# 7segment.net
KiCad netlist of a schematic drawn in EAGLE
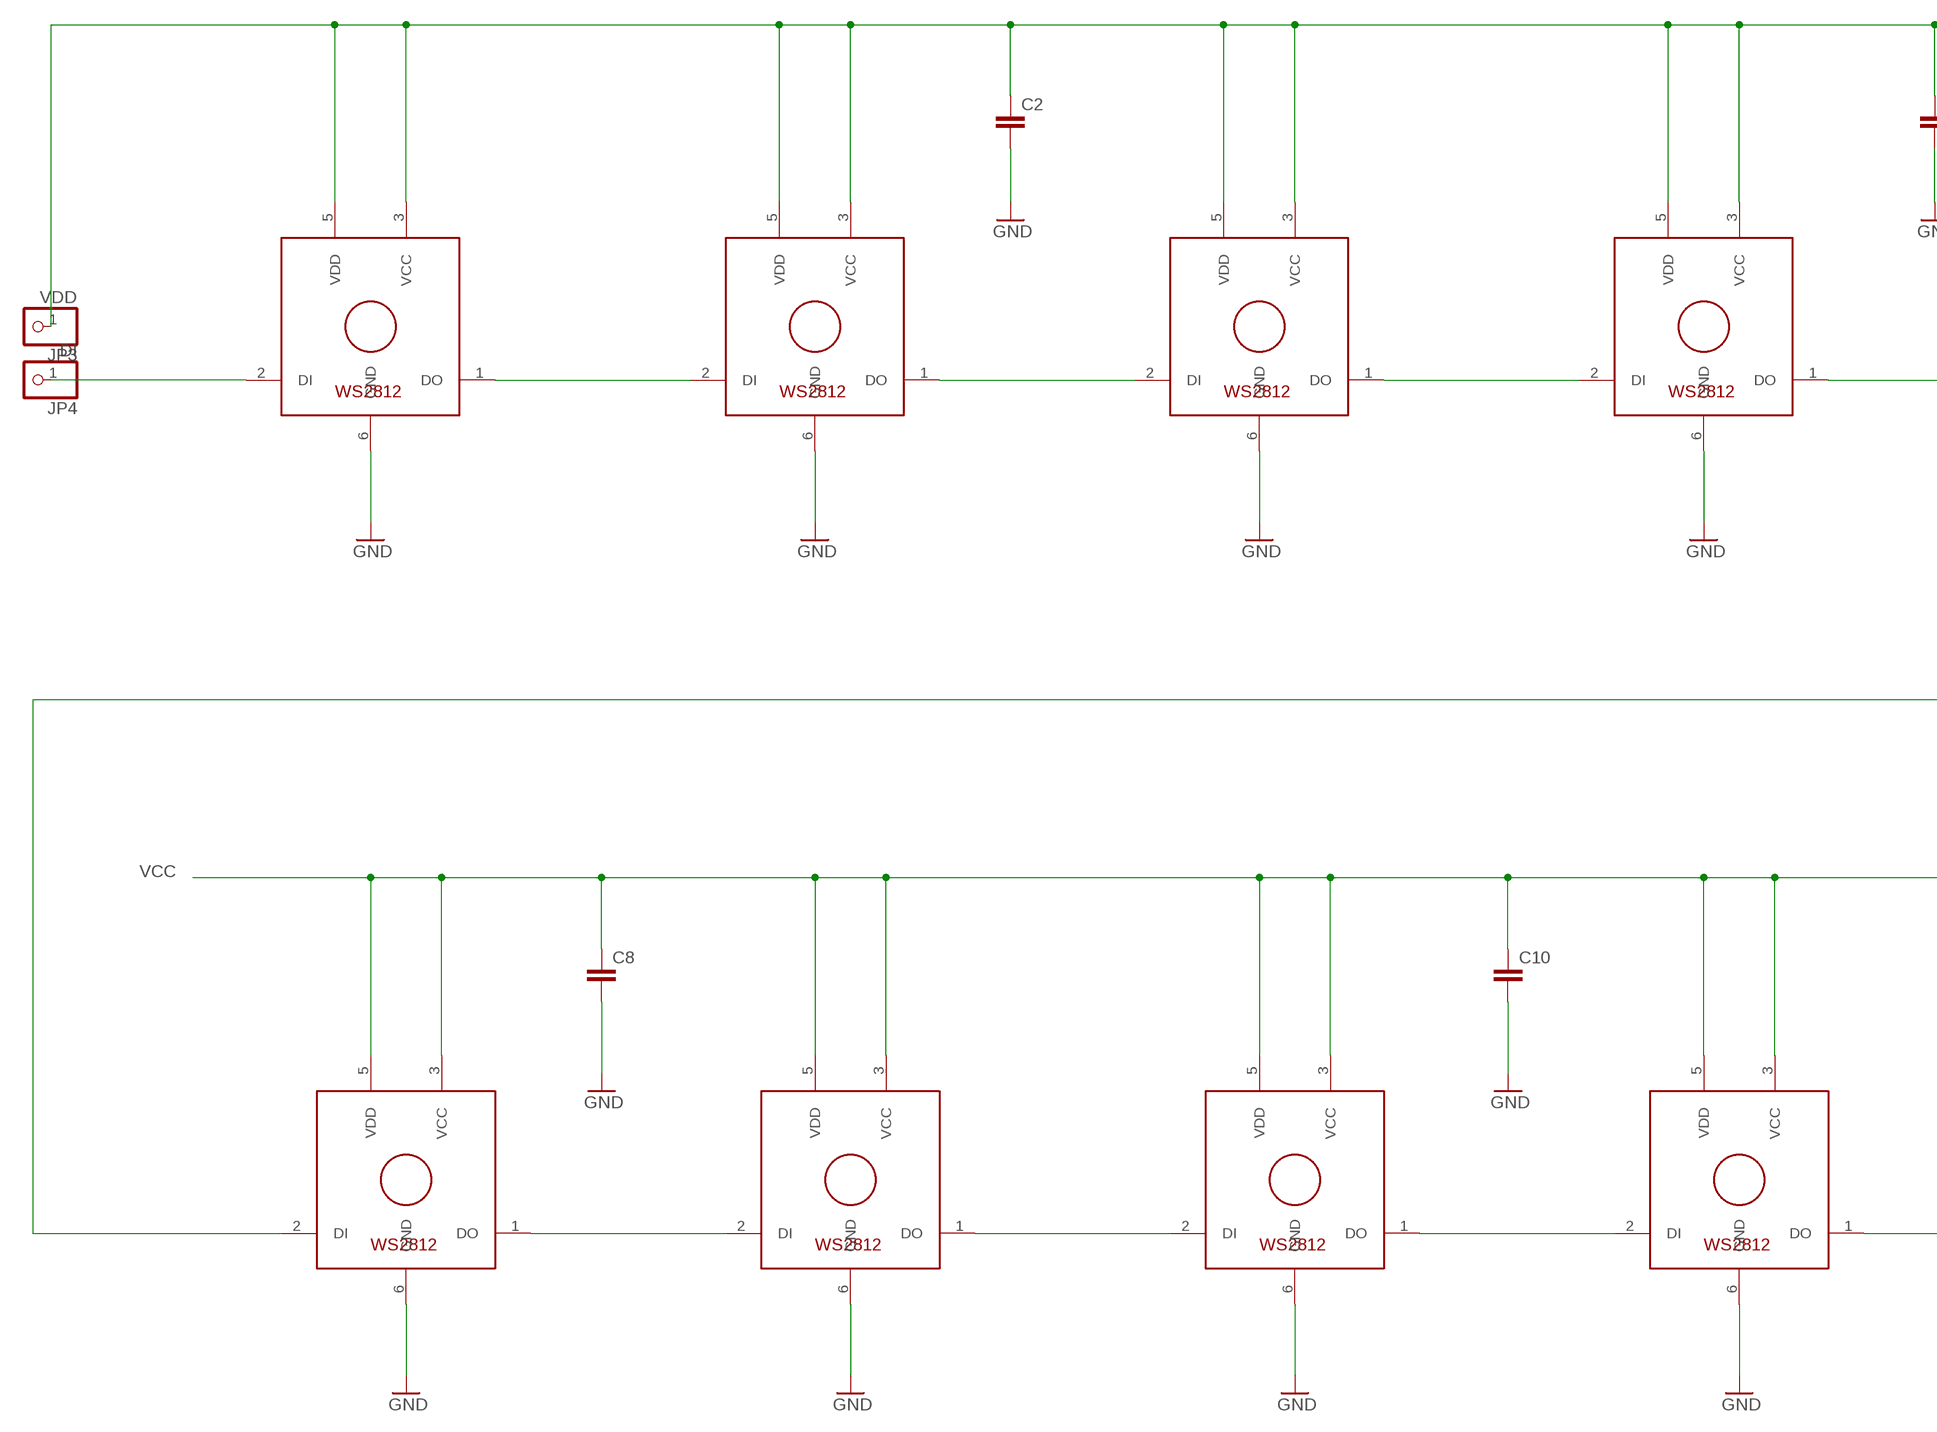
[diagram p0: schematic, sheet 1, part 1 of 2]
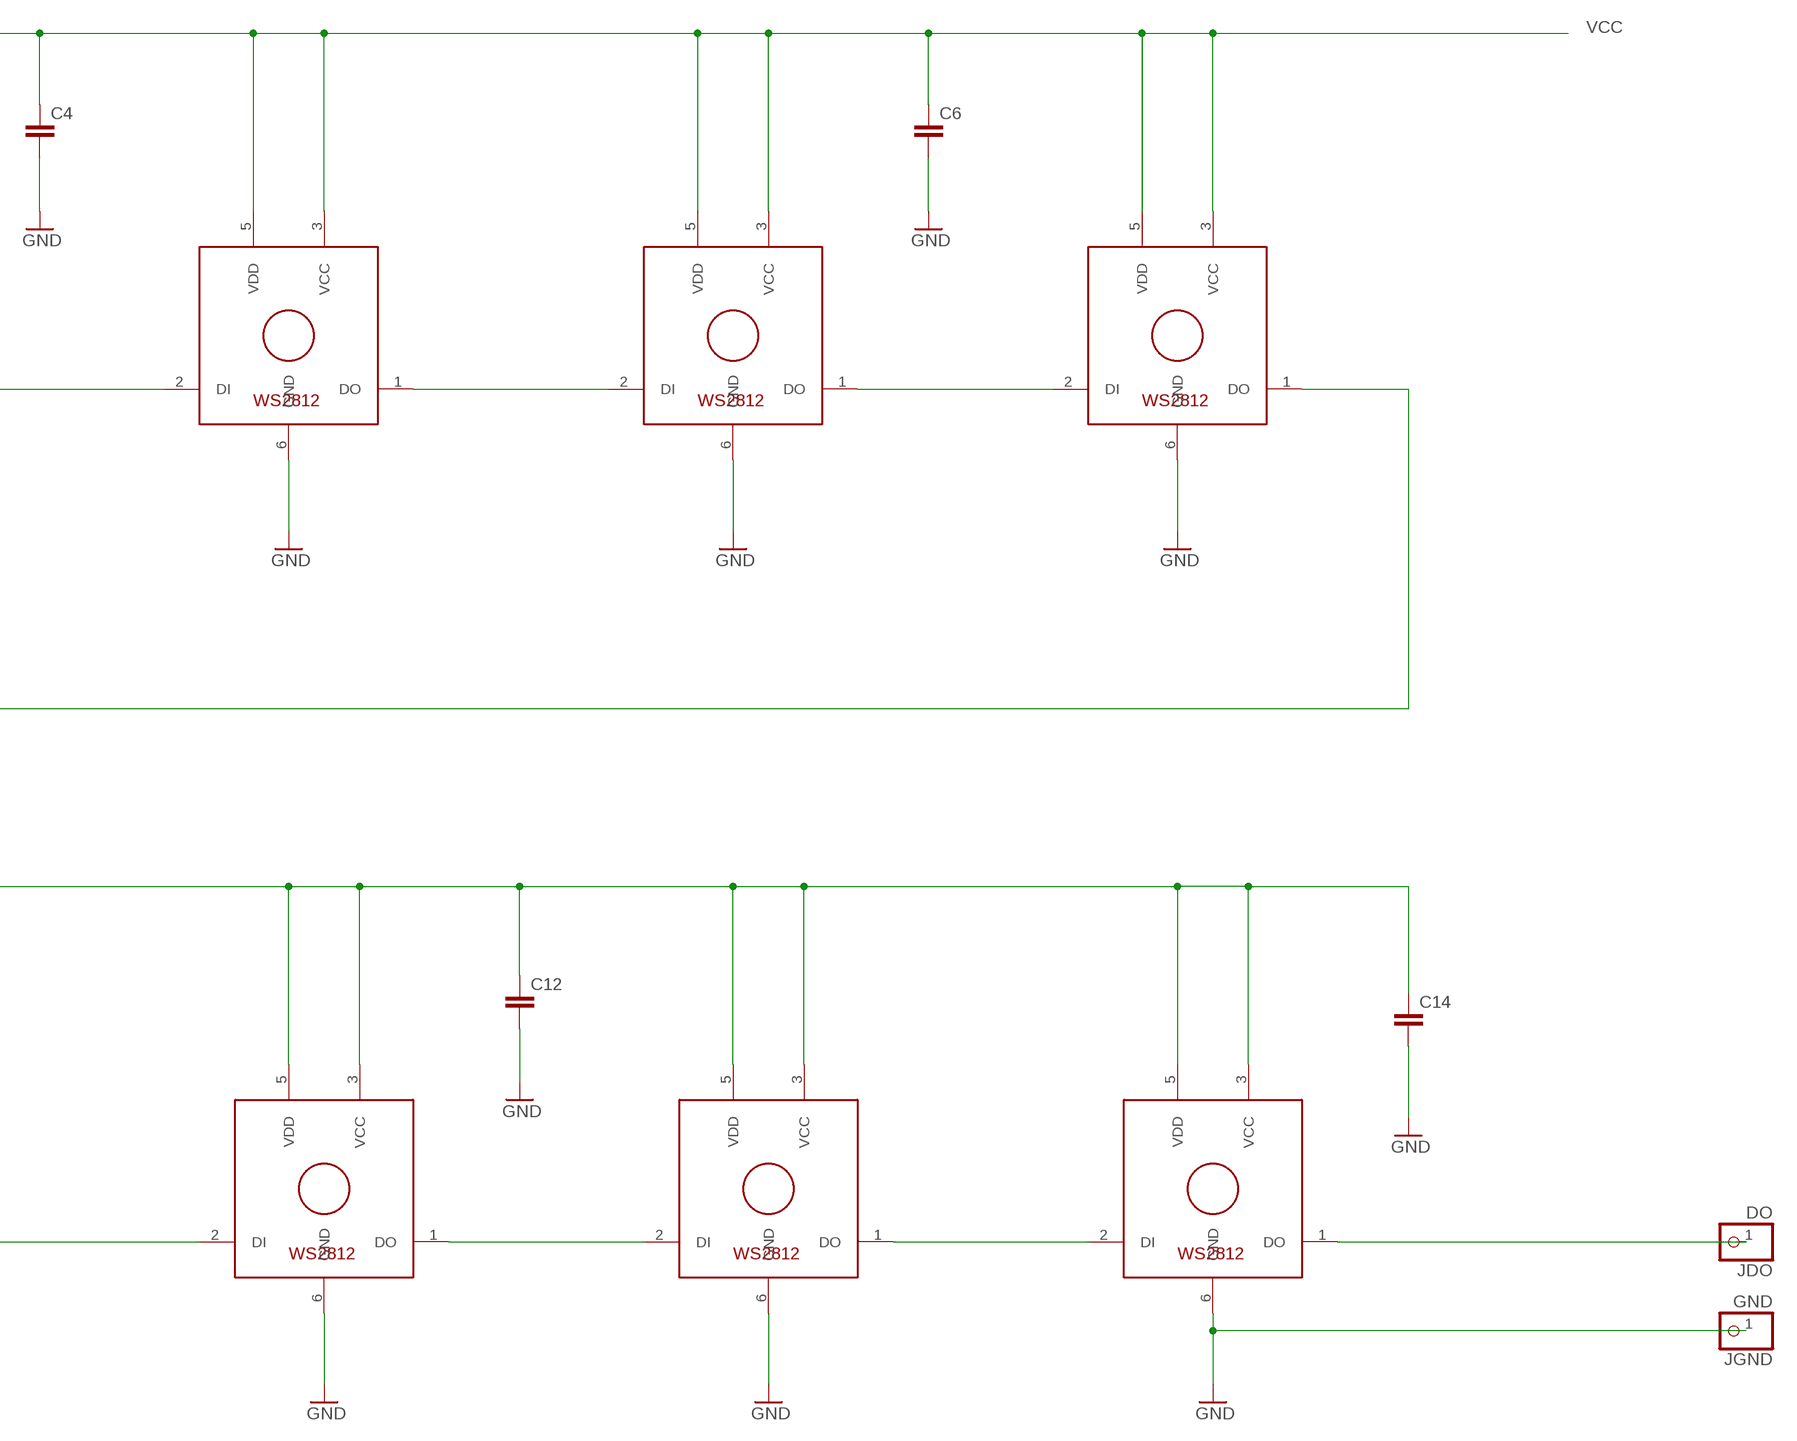
[diagram p1: schematic, sheet 1, part 2 of 2]

(export (version "E")
  (design (tool "Eeschema 10.0.6"))
  (components
    (comp (ref "C2")
      (value "C-EUC1206")
      (footprint "eagle-import:C1206")
      (libsource (lib "eagle-import") (part "C-EUC1206"))
    )
    (comp (ref "C4")
      (value "C-EUC1206")
      (footprint "eagle-import:C1206")
      (libsource (lib "eagle-import") (part "C-EUC1206"))
    )
    (comp (ref "C6")
      (value "C-EUC1206")
      (footprint "eagle-import:C1206")
      (libsource (lib "eagle-import") (part "C-EUC1206"))
    )
    (comp (ref "C8")
      (value "C-EUC1206")
      (footprint "eagle-import:C1206")
      (libsource (lib "eagle-import") (part "C-EUC1206"))
    )
    (comp (ref "C10")
      (value "C-EUC1206")
      (footprint "eagle-import:C1206")
      (libsource (lib "eagle-import") (part "C-EUC1206"))
    )
    (comp (ref "C12")
      (value "C-EUC1206")
      (footprint "eagle-import:C1206")
      (libsource (lib "eagle-import") (part "C-EUC1206"))
    )
    (comp (ref "C14")
      (value "C-EUC1206")
      (footprint "eagle-import:C1206")
      (libsource (lib "eagle-import") (part "C-EUC1206"))
    )
    (comp (ref "JDO")
      (value "DO")
      (footprint "eagle-import:1X01")
      (libsource (lib "eagle-import") (part "PINHD-1X1"))
    )
    (comp (ref "JGND")
      (value "GND")
      (footprint "eagle-import:1X01")
      (libsource (lib "eagle-import") (part "PINHD-1X1"))
    )
    (comp (ref "JP3")
      (value "VDD")
      (footprint "eagle-import:1X01")
      (libsource (lib "eagle-import") (part "PINHD-1X1"))
    )
    (comp (ref "JP4")
      (value "DI")
      (footprint "eagle-import:1X01")
      (libsource (lib "eagle-import") (part "PINHD-1X1"))
    )
    (comp (ref "U1")
      (value "WS2812")
      (footprint "eagle-import:WS2812")
      (libsource (lib "eagle-import") (part "WS2812"))
    )
    (comp (ref "U2")
      (value "WS2812")
      (footprint "eagle-import:WS2812")
      (libsource (lib "eagle-import") (part "WS2812"))
    )
    (comp (ref "U3")
      (value "WS2812")
      (footprint "eagle-import:WS2812")
      (libsource (lib "eagle-import") (part "WS2812"))
    )
    (comp (ref "U4")
      (value "WS2812")
      (footprint "eagle-import:WS2812")
      (libsource (lib "eagle-import") (part "WS2812"))
    )
    (comp (ref "U5")
      (value "WS2812")
      (footprint "eagle-import:WS2812")
      (libsource (lib "eagle-import") (part "WS2812"))
    )
    (comp (ref "U6")
      (value "WS2812")
      (footprint "eagle-import:WS2812")
      (libsource (lib "eagle-import") (part "WS2812"))
    )
    (comp (ref "U7")
      (value "WS2812")
      (footprint "eagle-import:WS2812")
      (libsource (lib "eagle-import") (part "WS2812"))
    )
    (comp (ref "U8")
      (value "WS2812")
      (footprint "eagle-import:WS2812")
      (libsource (lib "eagle-import") (part "WS2812"))
    )
    (comp (ref "U9")
      (value "WS2812")
      (footprint "eagle-import:WS2812")
      (libsource (lib "eagle-import") (part "WS2812"))
    )
    (comp (ref "U10")
      (value "WS2812")
      (footprint "eagle-import:WS2812")
      (libsource (lib "eagle-import") (part "WS2812"))
    )
    (comp (ref "U11")
      (value "WS2812")
      (footprint "eagle-import:WS2812")
      (libsource (lib "eagle-import") (part "WS2812"))
    )
    (comp (ref "U12")
      (value "WS2812")
      (footprint "eagle-import:WS2812")
      (libsource (lib "eagle-import") (part "WS2812"))
    )
    (comp (ref "U13")
      (value "WS2812")
      (footprint "eagle-import:WS2812")
      (libsource (lib "eagle-import") (part "WS2812"))
    )
    (comp (ref "U14")
      (value "WS2812")
      (footprint "eagle-import:WS2812")
      (libsource (lib "eagle-import") (part "WS2812"))
    )
  )
  (nets
    (net (code "1") (name "/VCC") (class "Default")
      (node (ref "C10") (pin "1") (pinfunction "1_1") (pintype "passive"))
      (node (ref "C12") (pin "1") (pinfunction "1_1") (pintype "passive"))
      (node (ref "C14") (pin "1") (pinfunction "1_1") (pintype "passive"))
      (node (ref "C2") (pin "1") (pinfunction "1_1") (pintype "passive"))
      (node (ref "C4") (pin "1") (pinfunction "1_1") (pintype "passive"))
      (node (ref "C6") (pin "1") (pinfunction "1_1") (pintype "passive"))
      (node (ref "C8") (pin "1") (pinfunction "1_1") (pintype "passive"))
      (node (ref "JP3") (pin "1") (pinfunction "1_1") (pintype "passive"))
      (node (ref "U1") (pin "3") (pinfunction "VCC_3") (pintype "power_in"))
      (node (ref "U1") (pin "5") (pinfunction "VDD_5") (pintype "power_in"))
      (node (ref "U10") (pin "3") (pinfunction "VCC_3") (pintype "power_in"))
      (node (ref "U10") (pin "5") (pinfunction "VDD_5") (pintype "power_in"))
      (node (ref "U11") (pin "3") (pinfunction "VCC_3") (pintype "power_in"))
      (node (ref "U11") (pin "5") (pinfunction "VDD_5") (pintype "power_in"))
      (node (ref "U12") (pin "3") (pinfunction "VCC_3") (pintype "power_in"))
      (node (ref "U12") (pin "5") (pinfunction "VDD_5") (pintype "power_in"))
      (node (ref "U13") (pin "3") (pinfunction "VCC_3") (pintype "power_in"))
      (node (ref "U13") (pin "5") (pinfunction "VDD_5") (pintype "power_in"))
      (node (ref "U14") (pin "3") (pinfunction "VCC_3") (pintype "power_in"))
      (node (ref "U14") (pin "5") (pinfunction "VDD_5") (pintype "power_in"))
      (node (ref "U2") (pin "3") (pinfunction "VCC_3") (pintype "power_in"))
      (node (ref "U2") (pin "5") (pinfunction "VDD_5") (pintype "power_in"))
      (node (ref "U3") (pin "3") (pinfunction "VCC_3") (pintype "power_in"))
      (node (ref "U3") (pin "5") (pinfunction "VDD_5") (pintype "power_in"))
      (node (ref "U4") (pin "3") (pinfunction "VCC_3") (pintype "power_in"))
      (node (ref "U4") (pin "5") (pinfunction "VDD_5") (pintype "power_in"))
      (node (ref "U5") (pin "3") (pinfunction "VCC_3") (pintype "power_in"))
      (node (ref "U5") (pin "5") (pinfunction "VDD_5") (pintype "power_in"))
      (node (ref "U6") (pin "3") (pinfunction "VCC_3") (pintype "power_in"))
      (node (ref "U6") (pin "5") (pinfunction "VDD_5") (pintype "power_in"))
      (node (ref "U7") (pin "3") (pinfunction "VCC_3") (pintype "power_in"))
      (node (ref "U7") (pin "5") (pinfunction "VDD_5") (pintype "power_in"))
      (node (ref "U8") (pin "3") (pinfunction "VCC_3") (pintype "power_in"))
      (node (ref "U8") (pin "5") (pinfunction "VDD_5") (pintype "power_in"))
      (node (ref "U9") (pin "3") (pinfunction "VCC_3") (pintype "power_in"))
      (node (ref "U9") (pin "5") (pinfunction "VDD_5") (pintype "power_in"))
    )
    (net (code "2") (name "GND") (class "Default")
      (node (ref "C10") (pin "2") (pinfunction "2_2") (pintype "passive"))
      (node (ref "C12") (pin "2") (pinfunction "2_2") (pintype "passive"))
      (node (ref "C14") (pin "2") (pinfunction "2_2") (pintype "passive"))
      (node (ref "C2") (pin "2") (pinfunction "2_2") (pintype "passive"))
      (node (ref "C4") (pin "2") (pinfunction "2_2") (pintype "passive"))
      (node (ref "C6") (pin "2") (pinfunction "2_2") (pintype "passive"))
      (node (ref "C8") (pin "2") (pinfunction "2_2") (pintype "passive"))
      (node (ref "JGND") (pin "1") (pinfunction "1_1") (pintype "passive"))
      (node (ref "U1") (pin "6") (pinfunction "GND_6") (pintype "power_in"))
      (node (ref "U10") (pin "6") (pinfunction "GND_6") (pintype "power_in"))
      (node (ref "U11") (pin "6") (pinfunction "GND_6") (pintype "power_in"))
      (node (ref "U12") (pin "6") (pinfunction "GND_6") (pintype "power_in"))
      (node (ref "U13") (pin "6") (pinfunction "GND_6") (pintype "power_in"))
      (node (ref "U14") (pin "6") (pinfunction "GND_6") (pintype "power_in"))
      (node (ref "U2") (pin "6") (pinfunction "GND_6") (pintype "power_in"))
      (node (ref "U3") (pin "6") (pinfunction "GND_6") (pintype "power_in"))
      (node (ref "U4") (pin "6") (pinfunction "GND_6") (pintype "power_in"))
      (node (ref "U5") (pin "6") (pinfunction "GND_6") (pintype "power_in"))
      (node (ref "U6") (pin "6") (pinfunction "GND_6") (pintype "power_in"))
      (node (ref "U7") (pin "6") (pinfunction "GND_6") (pintype "power_in"))
      (node (ref "U8") (pin "6") (pinfunction "GND_6") (pintype "power_in"))
      (node (ref "U9") (pin "6") (pinfunction "GND_6") (pintype "power_in"))
    )
    (net (code "3") (name "Net-(U1-DI)") (class "Default")
      (node (ref "JP4") (pin "1") (pinfunction "1_1") (pintype "passive"))
      (node (ref "U1") (pin "2") (pinfunction "DI_2") (pintype "input"))
    )
    (net (code "4") (name "Net-(U1-DO)") (class "Default")
      (node (ref "U1") (pin "1") (pinfunction "DO_1") (pintype "output"))
      (node (ref "U2") (pin "2") (pinfunction "DI_2") (pintype "input"))
    )
    (net (code "5") (name "Net-(U2-DO)") (class "Default")
      (node (ref "U2") (pin "1") (pinfunction "DO_1") (pintype "output"))
      (node (ref "U3") (pin "2") (pinfunction "DI_2") (pintype "input"))
    )
    (net (code "6") (name "Net-(U3-DO)") (class "Default")
      (node (ref "U3") (pin "1") (pinfunction "DO_1") (pintype "output"))
      (node (ref "U4") (pin "2") (pinfunction "DI_2") (pintype "input"))
    )
    (net (code "7") (name "Net-(U4-DO)") (class "Default")
      (node (ref "U4") (pin "1") (pinfunction "DO_1") (pintype "output"))
      (node (ref "U5") (pin "2") (pinfunction "DI_2") (pintype "input"))
    )
    (net (code "8") (name "Net-(U5-DO)") (class "Default")
      (node (ref "U5") (pin "1") (pinfunction "DO_1") (pintype "output"))
      (node (ref "U6") (pin "2") (pinfunction "DI_2") (pintype "input"))
    )
    (net (code "9") (name "Net-(U6-DO)") (class "Default")
      (node (ref "U6") (pin "1") (pinfunction "DO_1") (pintype "output"))
      (node (ref "U7") (pin "2") (pinfunction "DI_2") (pintype "input"))
    )
    (net (code "10") (name "Net-(U7-DO)") (class "Default")
      (node (ref "U7") (pin "1") (pinfunction "DO_1") (pintype "output"))
      (node (ref "U8") (pin "2") (pinfunction "DI_2") (pintype "input"))
    )
    (net (code "11") (name "Net-(U8-DO)") (class "Default")
      (node (ref "U8") (pin "1") (pinfunction "DO_1") (pintype "output"))
      (node (ref "U9") (pin "2") (pinfunction "DI_2") (pintype "input"))
    )
    (net (code "12") (name "Net-(U10-DI)") (class "Default")
      (node (ref "U10") (pin "2") (pinfunction "DI_2") (pintype "input"))
      (node (ref "U9") (pin "1") (pinfunction "DO_1") (pintype "output"))
    )
    (net (code "13") (name "Net-(U10-DO)") (class "Default")
      (node (ref "U10") (pin "1") (pinfunction "DO_1") (pintype "output"))
      (node (ref "U11") (pin "2") (pinfunction "DI_2") (pintype "input"))
    )
    (net (code "14") (name "Net-(U11-DO)") (class "Default")
      (node (ref "U11") (pin "1") (pinfunction "DO_1") (pintype "output"))
      (node (ref "U12") (pin "2") (pinfunction "DI_2") (pintype "input"))
    )
    (net (code "15") (name "Net-(U12-DO)") (class "Default")
      (node (ref "U12") (pin "1") (pinfunction "DO_1") (pintype "output"))
      (node (ref "U13") (pin "2") (pinfunction "DI_2") (pintype "input"))
    )
    (net (code "16") (name "Net-(U13-DO)") (class "Default")
      (node (ref "U13") (pin "1") (pinfunction "DO_1") (pintype "output"))
      (node (ref "U14") (pin "2") (pinfunction "DI_2") (pintype "input"))
    )
    (net (code "17") (name "Net-(U14-DO)") (class "Default")
      (node (ref "JDO") (pin "1") (pinfunction "1_1") (pintype "passive"))
      (node (ref "U14") (pin "1") (pinfunction "DO_1") (pintype "output"))
    )
  )
)
